# SOIC28-TSSOP28_v1_0.net
KiCad netlist of a schematic drawn in EAGLE
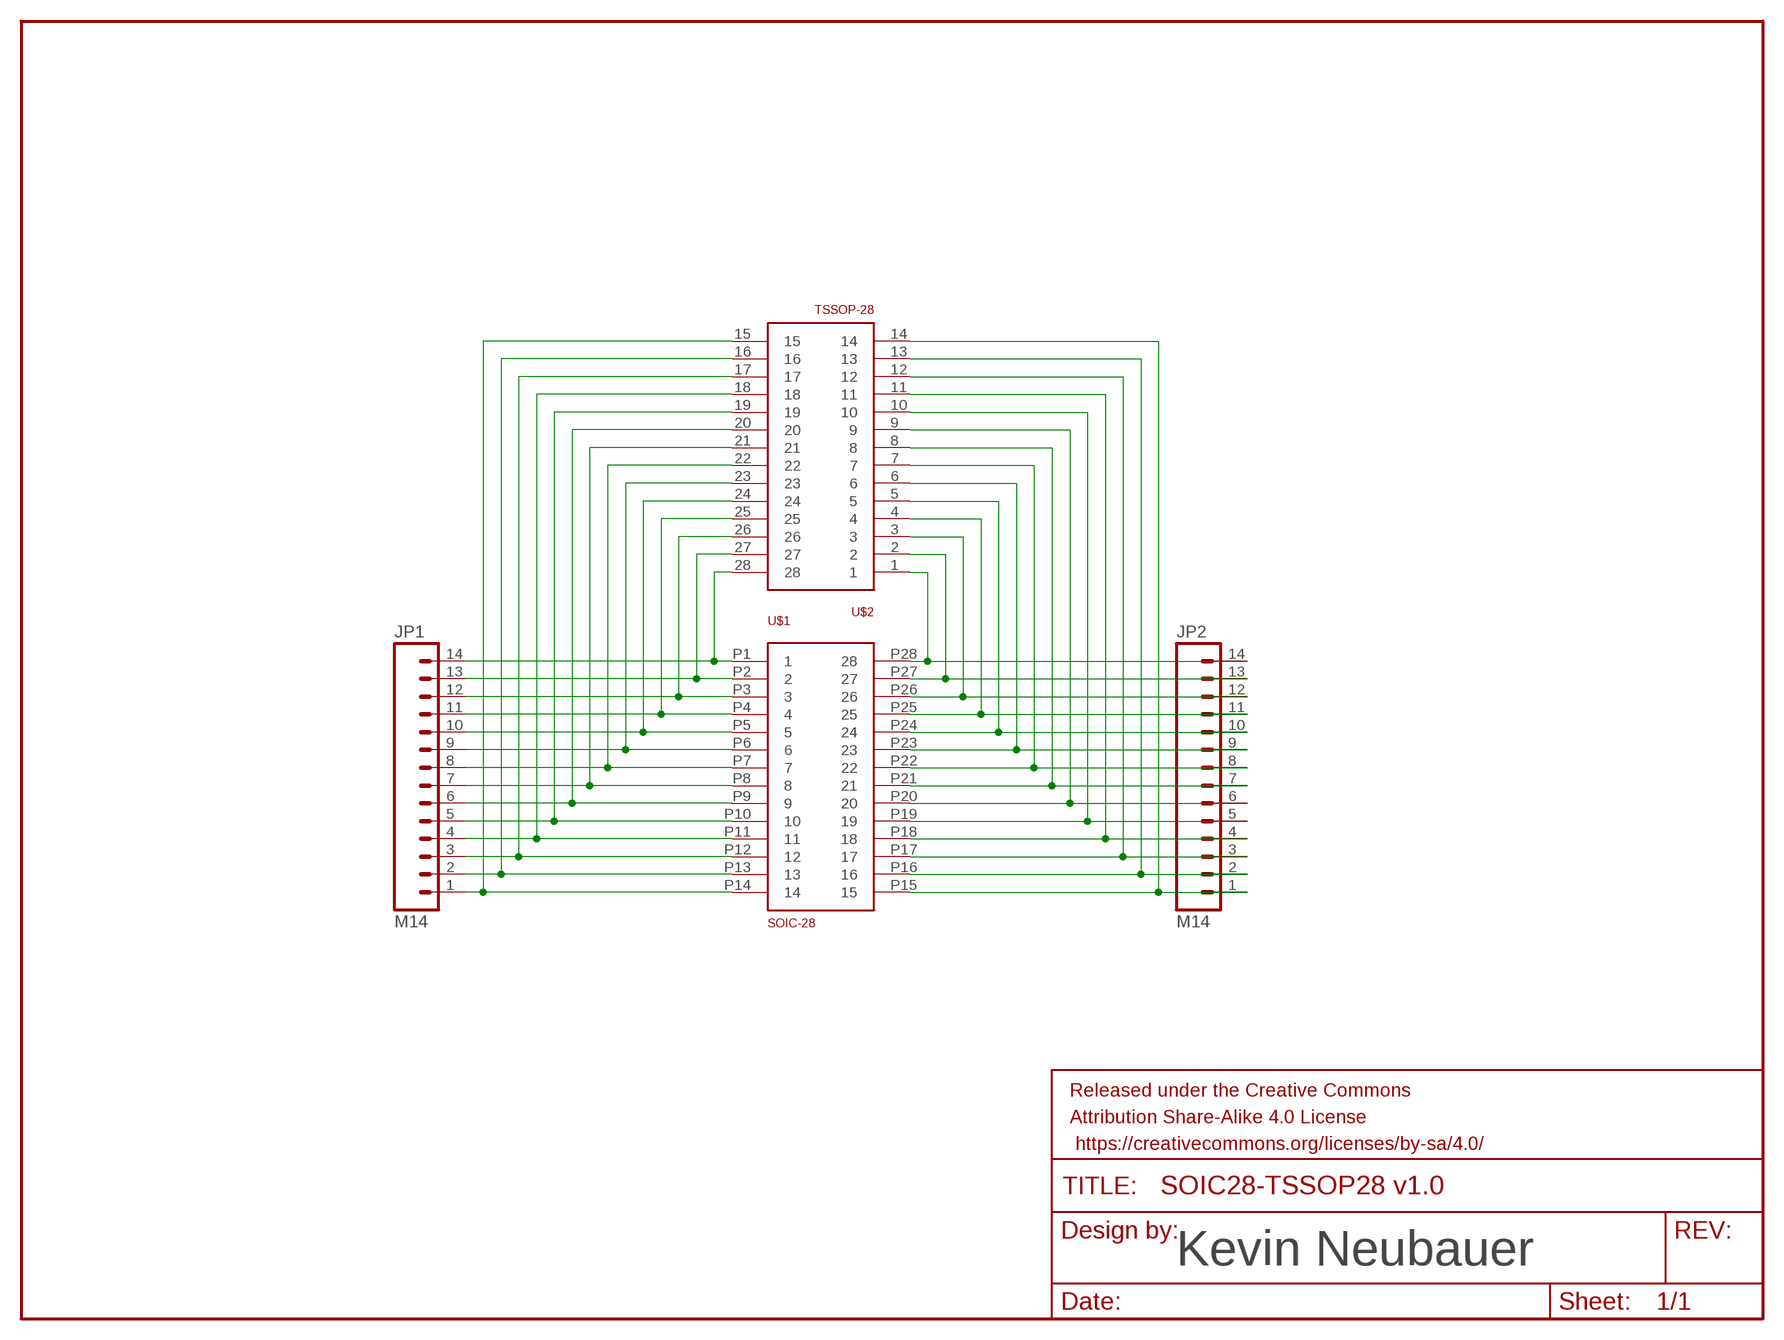
[diagram p0: schematic, sheet 1]

(export (version "E")
  (design (tool "Eeschema 10.0.6"))
  (components
    (comp (ref "FRAME1")
      (value "FRAME-LETTER")
      (footprint "eagle-import:CREATIVE_COMMONS")
      (libsource (lib "eagle-import") (part "FRAME-LETTER"))
    )
    (comp (ref "JP1")
      (value "M14")
      (footprint "eagle-import:1X14")
      (libsource (lib "eagle-import") (part "M14"))
    )
    (comp (ref "JP2")
      (value "M14")
      (footprint "eagle-import:1X14")
      (libsource (lib "eagle-import") (part "M14"))
    )
    (comp (ref "U$1")
      (value "SOIC-28")
      (footprint "eagle-import:SOIC-28")
      (libsource (lib "eagle-import") (part "SOIC-28"))
    )
    (comp (ref "U$2")
      (value "TSSOP-28")
      (footprint "eagle-import:TSSOP28")
      (libsource (lib "eagle-import") (part "TSSOP-28"))
    )
  )
  (nets
    (net (code "1") (name "Net-(U$1-1)") (class "Default")
      (node (ref "JP1") (pin "14") (pinfunction "14_14") (pintype "passive"))
      (node (ref "U$1") (pin "P1") (pinfunction "1_P1") (pintype "bidirectional"))
      (node (ref "U$2") (pin "28") (pinfunction "28_28") (pintype "bidirectional"))
    )
    (net (code "2") (name "Net-(U$1-2)") (class "Default")
      (node (ref "JP1") (pin "13") (pinfunction "13_13") (pintype "passive"))
      (node (ref "U$1") (pin "P2") (pinfunction "2_P2") (pintype "bidirectional"))
      (node (ref "U$2") (pin "27") (pinfunction "27_27") (pintype "bidirectional"))
    )
    (net (code "3") (name "Net-(U$1-3)") (class "Default")
      (node (ref "JP1") (pin "12") (pinfunction "12_12") (pintype "passive"))
      (node (ref "U$1") (pin "P3") (pinfunction "3_P3") (pintype "bidirectional"))
      (node (ref "U$2") (pin "26") (pinfunction "26_26") (pintype "bidirectional"))
    )
    (net (code "4") (name "Net-(U$1-4)") (class "Default")
      (node (ref "JP1") (pin "11") (pinfunction "11_11") (pintype "passive"))
      (node (ref "U$1") (pin "P4") (pinfunction "4_P4") (pintype "bidirectional"))
      (node (ref "U$2") (pin "25") (pinfunction "25_25") (pintype "bidirectional"))
    )
    (net (code "5") (name "Net-(U$1-5)") (class "Default")
      (node (ref "JP1") (pin "10") (pinfunction "10_10") (pintype "passive"))
      (node (ref "U$1") (pin "P5") (pinfunction "5_P5") (pintype "bidirectional"))
      (node (ref "U$2") (pin "24") (pinfunction "24_24") (pintype "bidirectional"))
    )
    (net (code "6") (name "Net-(U$1-6)") (class "Default")
      (node (ref "JP1") (pin "9") (pinfunction "9_9") (pintype "passive"))
      (node (ref "U$1") (pin "P6") (pinfunction "6_P6") (pintype "bidirectional"))
      (node (ref "U$2") (pin "23") (pinfunction "23_23") (pintype "bidirectional"))
    )
    (net (code "7") (name "Net-(U$1-7)") (class "Default")
      (node (ref "JP1") (pin "8") (pinfunction "8_8") (pintype "passive"))
      (node (ref "U$1") (pin "P7") (pinfunction "7_P7") (pintype "bidirectional"))
      (node (ref "U$2") (pin "22") (pinfunction "22_22") (pintype "bidirectional"))
    )
    (net (code "8") (name "Net-(U$1-8)") (class "Default")
      (node (ref "JP1") (pin "7") (pinfunction "7_7") (pintype "passive"))
      (node (ref "U$1") (pin "P8") (pinfunction "8_P8") (pintype "bidirectional"))
      (node (ref "U$2") (pin "21") (pinfunction "21_21") (pintype "bidirectional"))
    )
    (net (code "9") (name "Net-(U$1-9)") (class "Default")
      (node (ref "JP1") (pin "6") (pinfunction "6_6") (pintype "passive"))
      (node (ref "U$1") (pin "P9") (pinfunction "9_P9") (pintype "bidirectional"))
      (node (ref "U$2") (pin "20") (pinfunction "20_20") (pintype "bidirectional"))
    )
    (net (code "10") (name "Net-(U$1-10)") (class "Default")
      (node (ref "JP1") (pin "5") (pinfunction "5_5") (pintype "passive"))
      (node (ref "U$1") (pin "P10") (pinfunction "10_P10") (pintype "bidirectional"))
      (node (ref "U$2") (pin "19") (pinfunction "19_19") (pintype "bidirectional"))
    )
    (net (code "11") (name "Net-(U$1-11)") (class "Default")
      (node (ref "JP1") (pin "4") (pinfunction "4_4") (pintype "passive"))
      (node (ref "U$1") (pin "P11") (pinfunction "11_P11") (pintype "bidirectional"))
      (node (ref "U$2") (pin "18") (pinfunction "18_18") (pintype "bidirectional"))
    )
    (net (code "12") (name "Net-(U$1-12)") (class "Default")
      (node (ref "JP1") (pin "3") (pinfunction "3_3") (pintype "passive"))
      (node (ref "U$1") (pin "P12") (pinfunction "12_P12") (pintype "bidirectional"))
      (node (ref "U$2") (pin "17") (pinfunction "17_17") (pintype "bidirectional"))
    )
    (net (code "13") (name "Net-(U$1-13)") (class "Default")
      (node (ref "JP1") (pin "2") (pinfunction "2_2") (pintype "passive"))
      (node (ref "U$1") (pin "P13") (pinfunction "13_P13") (pintype "bidirectional"))
      (node (ref "U$2") (pin "16") (pinfunction "16_16") (pintype "bidirectional"))
    )
    (net (code "14") (name "Net-(U$1-14)") (class "Default")
      (node (ref "JP1") (pin "1") (pinfunction "1_1") (pintype "passive"))
      (node (ref "U$1") (pin "P14") (pinfunction "14_P14") (pintype "bidirectional"))
      (node (ref "U$2") (pin "15") (pinfunction "15_15") (pintype "bidirectional"))
    )
    (net (code "15") (name "Net-(U$1-15)") (class "Default")
      (node (ref "JP2") (pin "1") (pinfunction "1_1") (pintype "passive"))
      (node (ref "U$1") (pin "P15") (pinfunction "15_P15") (pintype "bidirectional"))
      (node (ref "U$2") (pin "14") (pinfunction "14_14") (pintype "bidirectional"))
    )
    (net (code "16") (name "Net-(U$1-16)") (class "Default")
      (node (ref "JP2") (pin "2") (pinfunction "2_2") (pintype "passive"))
      (node (ref "U$1") (pin "P16") (pinfunction "16_P16") (pintype "bidirectional"))
      (node (ref "U$2") (pin "13") (pinfunction "13_13") (pintype "bidirectional"))
    )
    (net (code "17") (name "Net-(U$1-17)") (class "Default")
      (node (ref "JP2") (pin "3") (pinfunction "3_3") (pintype "passive"))
      (node (ref "U$1") (pin "P17") (pinfunction "17_P17") (pintype "bidirectional"))
      (node (ref "U$2") (pin "12") (pinfunction "12_12") (pintype "bidirectional"))
    )
    (net (code "18") (name "Net-(U$1-18)") (class "Default")
      (node (ref "JP2") (pin "4") (pinfunction "4_4") (pintype "passive"))
      (node (ref "U$1") (pin "P18") (pinfunction "18_P18") (pintype "bidirectional"))
      (node (ref "U$2") (pin "11") (pinfunction "11_11") (pintype "bidirectional"))
    )
    (net (code "19") (name "Net-(U$1-19)") (class "Default")
      (node (ref "JP2") (pin "5") (pinfunction "5_5") (pintype "passive"))
      (node (ref "U$1") (pin "P19") (pinfunction "19_P19") (pintype "bidirectional"))
      (node (ref "U$2") (pin "10") (pinfunction "10_10") (pintype "bidirectional"))
    )
    (net (code "20") (name "Net-(U$1-20)") (class "Default")
      (node (ref "JP2") (pin "6") (pinfunction "6_6") (pintype "passive"))
      (node (ref "U$1") (pin "P20") (pinfunction "20_P20") (pintype "bidirectional"))
      (node (ref "U$2") (pin "9") (pinfunction "9_9") (pintype "bidirectional"))
    )
    (net (code "21") (name "Net-(U$1-21)") (class "Default")
      (node (ref "JP2") (pin "7") (pinfunction "7_7") (pintype "passive"))
      (node (ref "U$1") (pin "P21") (pinfunction "21_P21") (pintype "bidirectional"))
      (node (ref "U$2") (pin "8") (pinfunction "8_8") (pintype "bidirectional"))
    )
    (net (code "22") (name "Net-(U$1-22)") (class "Default")
      (node (ref "JP2") (pin "8") (pinfunction "8_8") (pintype "passive"))
      (node (ref "U$1") (pin "P22") (pinfunction "22_P22") (pintype "bidirectional"))
      (node (ref "U$2") (pin "7") (pinfunction "7_7") (pintype "bidirectional"))
    )
    (net (code "23") (name "Net-(U$1-23)") (class "Default")
      (node (ref "JP2") (pin "9") (pinfunction "9_9") (pintype "passive"))
      (node (ref "U$1") (pin "P23") (pinfunction "23_P23") (pintype "bidirectional"))
      (node (ref "U$2") (pin "6") (pinfunction "6_6") (pintype "bidirectional"))
    )
    (net (code "24") (name "Net-(U$1-24)") (class "Default")
      (node (ref "JP2") (pin "10") (pinfunction "10_10") (pintype "passive"))
      (node (ref "U$1") (pin "P24") (pinfunction "24_P24") (pintype "bidirectional"))
      (node (ref "U$2") (pin "5") (pinfunction "5_5") (pintype "bidirectional"))
    )
    (net (code "25") (name "Net-(U$1-25)") (class "Default")
      (node (ref "JP2") (pin "11") (pinfunction "11_11") (pintype "passive"))
      (node (ref "U$1") (pin "P25") (pinfunction "25_P25") (pintype "bidirectional"))
      (node (ref "U$2") (pin "4") (pinfunction "4_4") (pintype "bidirectional"))
    )
    (net (code "26") (name "Net-(U$1-26)") (class "Default")
      (node (ref "JP2") (pin "12") (pinfunction "12_12") (pintype "passive"))
      (node (ref "U$1") (pin "P26") (pinfunction "26_P26") (pintype "bidirectional"))
      (node (ref "U$2") (pin "3") (pinfunction "3_3") (pintype "bidirectional"))
    )
    (net (code "27") (name "Net-(U$1-27)") (class "Default")
      (node (ref "JP2") (pin "13") (pinfunction "13_13") (pintype "passive"))
      (node (ref "U$1") (pin "P27") (pinfunction "27_P27") (pintype "bidirectional"))
      (node (ref "U$2") (pin "2") (pinfunction "2_2") (pintype "bidirectional"))
    )
    (net (code "28") (name "Net-(U$1-28)") (class "Default")
      (node (ref "JP2") (pin "14") (pinfunction "14_14") (pintype "passive"))
      (node (ref "U$1") (pin "P28") (pinfunction "28_P28") (pintype "bidirectional"))
      (node (ref "U$2") (pin "1") (pinfunction "1_1") (pintype "bidirectional"))
    )
  )
)
